# HWProgUSB.net
KiCad netlist of a schematic drawn in EAGLE
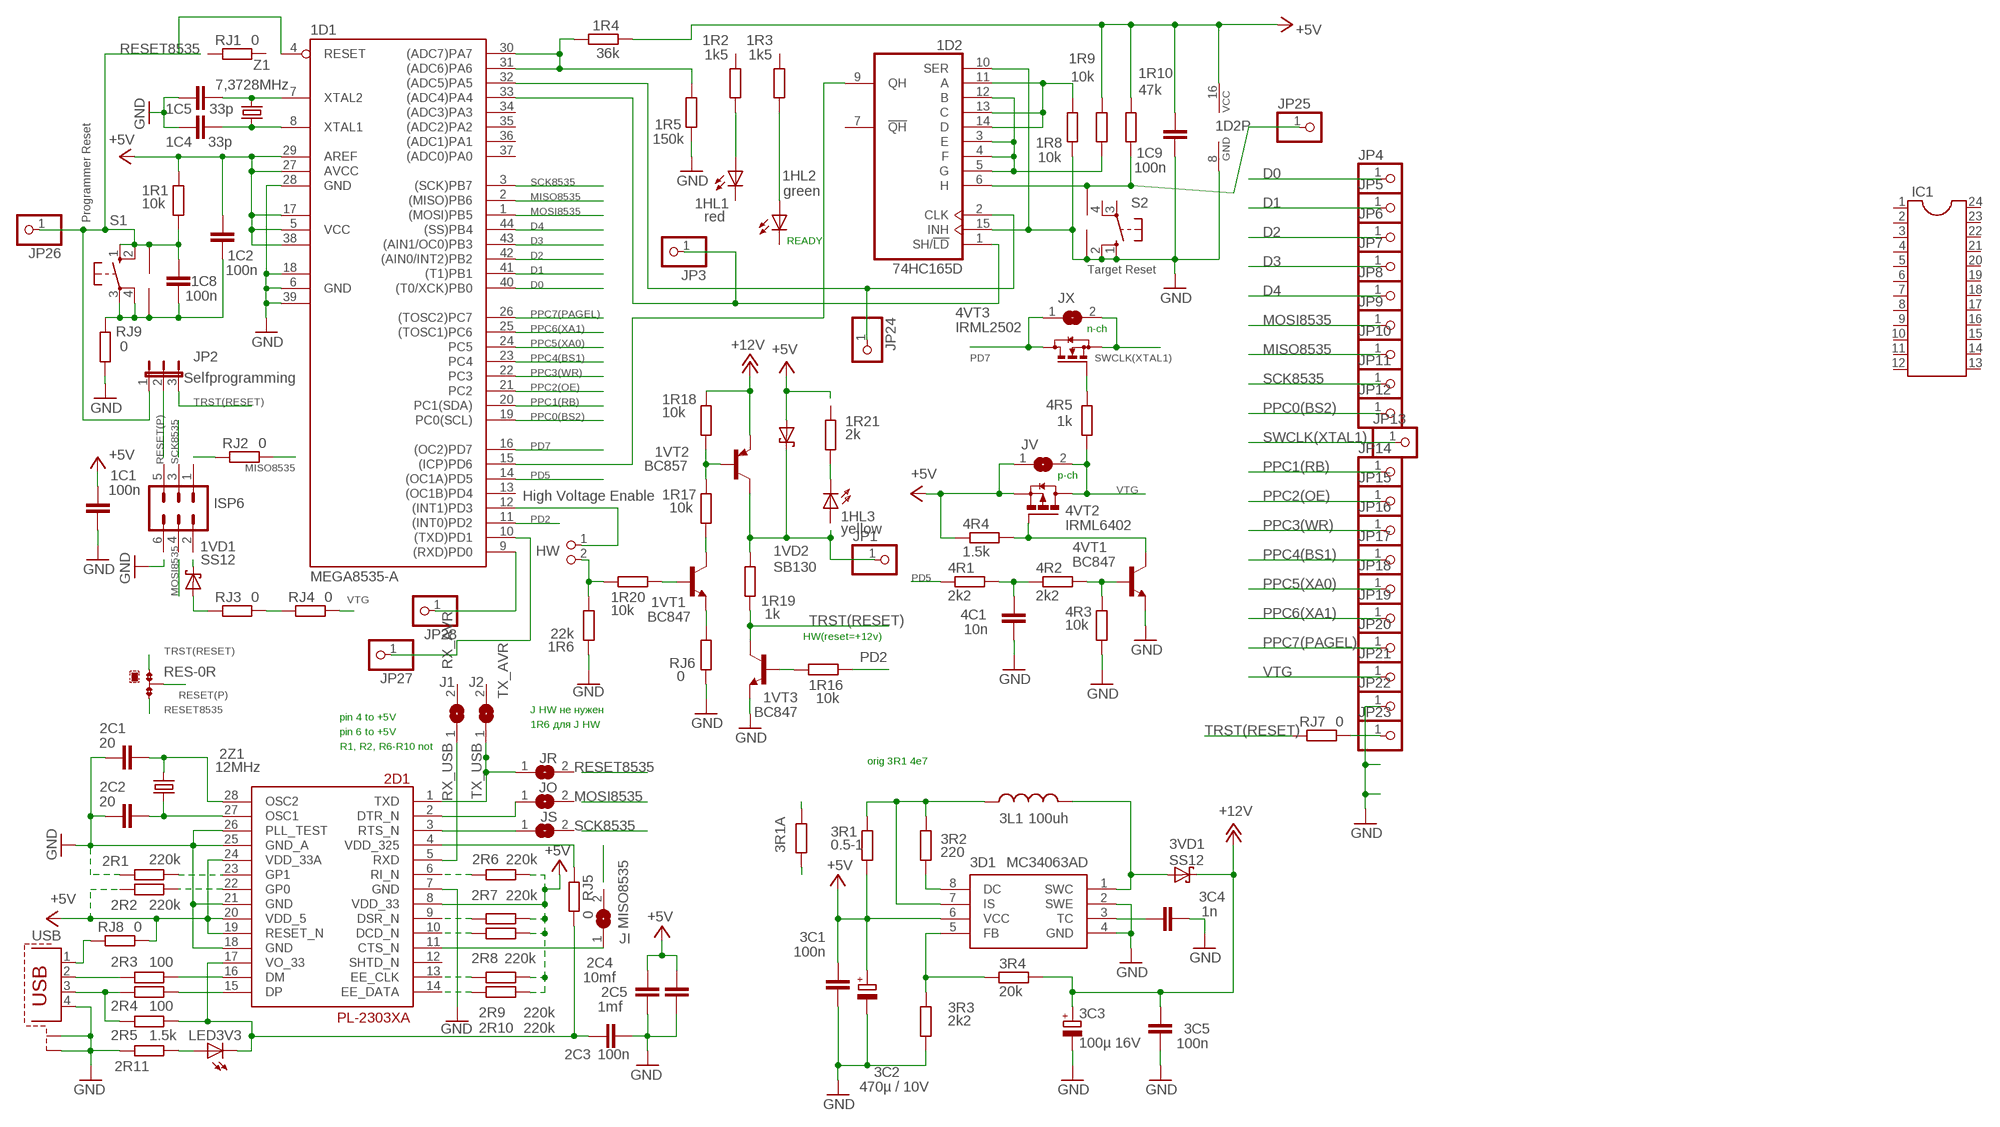
[diagram p0: schematic, sheet 1]

(export (version "E")
  (design (tool "Eeschema 10.0.6"))
  (components
    (comp (ref "1C1")
      (value "100n")
      (footprint "eagle-import:C0805")
      (libsource (lib "eagle-import") (part "rcl_C-EUC0805"))
    )
    (comp (ref "1C2")
      (value "100n")
      (footprint "eagle-import:C0805")
      (libsource (lib "eagle-import") (part "rcl_C-EUC0805"))
    )
    (comp (ref "1C4")
      (value "33p")
      (footprint "eagle-import:C0805")
      (libsource (lib "eagle-import") (part "rcl_C-EUC0805"))
    )
    (comp (ref "1C5")
      (value "33p")
      (footprint "eagle-import:C0805")
      (libsource (lib "eagle-import") (part "rcl_C-EUC0805"))
    )
    (comp (ref "1C8")
      (value "100n")
      (footprint "eagle-import:C0805")
      (libsource (lib "eagle-import") (part "rcl_C-EUC0805"))
    )
    (comp (ref "1C9")
      (value "100n")
      (footprint "eagle-import:C0805")
      (libsource (lib "eagle-import") (part "rcl_C-EUC0805"))
    )
    (comp (ref "1D1")
      (value "MEGA8535-A")
      (footprint "eagle-import:TQFP44")
      (fields (field (name "MPN") "ATMEGA8535-16AU"))
      (libsource (lib "eagle-import") (part "MEGA8535-A"))
    )
    (comp (ref "1D2")
      (value "74HC165D")
      (footprint "eagle-import:SO16")
      (libsource (lib "eagle-import") (part "74165DHC"))
    )
    (comp (ref "1HL1")
      (value "red")
      (footprint "eagle-import:LED5MM")
      (libsource (lib "eagle-import") (part "LED5MM"))
    )
    (comp (ref "1HL2")
      (value "green")
      (footprint "eagle-import:LED5MM")
      (libsource (lib "eagle-import") (part "LED5MM"))
    )
    (comp (ref "1HL3")
      (value "yellow")
      (footprint "eagle-import:LED5MM")
      (libsource (lib "eagle-import") (part "rc-elektronik_LED5MM"))
    )
    (comp (ref "1R1")
      (value "10k")
      (footprint "eagle-import:M0805")
      (libsource (lib "eagle-import") (part "R-EU_M0805"))
    )
    (comp (ref "1R2")
      (value "1k5")
      (footprint "eagle-import:M0805")
      (libsource (lib "eagle-import") (part "R-EU_M0805"))
    )
    (comp (ref "1R3")
      (value "1k5")
      (footprint "eagle-import:M0805")
      (libsource (lib "eagle-import") (part "R-EU_M0805"))
    )
    (comp (ref "1R4")
      (value "36k")
      (footprint "eagle-import:M0805")
      (libsource (lib "eagle-import") (part "R-EU_M0805"))
    )
    (comp (ref "1R5")
      (value "150k")
      (footprint "eagle-import:R1206")
      (libsource (lib "eagle-import") (part "R-EU_R1206"))
    )
    (comp (ref "1R6")
      (value "22k")
      (footprint "eagle-import:M1206")
      (libsource (lib "eagle-import") (part "R-EU_M1206"))
    )
    (comp (ref "1R8")
      (value "10k")
      (footprint "eagle-import:M0805")
      (libsource (lib "eagle-import") (part "R-EU_M0805"))
    )
    (comp (ref "1R9")
      (value "10k")
      (footprint "eagle-import:M0805")
      (libsource (lib "eagle-import") (part "R-EU_M0805"))
    )
    (comp (ref "1R10")
      (value "47k")
      (footprint "eagle-import:M0805")
      (libsource (lib "eagle-import") (part "R-EU_M0805"))
    )
    (comp (ref "1R16")
      (value "10k")
      (footprint "eagle-import:R0805")
      (libsource (lib "eagle-import") (part "R-EU_R0805"))
    )
    (comp (ref "1R17")
      (value "10k")
      (footprint "eagle-import:M0805")
      (libsource (lib "eagle-import") (part "R-EU_M0805"))
    )
    (comp (ref "1R18")
      (value "10k")
      (footprint "eagle-import:M0805")
      (libsource (lib "eagle-import") (part "R-EU_M0805"))
    )
    (comp (ref "1R19")
      (value "1k")
      (footprint "eagle-import:M0805")
      (libsource (lib "eagle-import") (part "R-EU_M0805"))
    )
    (comp (ref "1R20")
      (value "10k")
      (footprint "eagle-import:M0805")
      (libsource (lib "eagle-import") (part "R-EU_M0805"))
    )
    (comp (ref "1R21")
      (value "2k")
      (footprint "eagle-import:R1206W")
      (libsource (lib "eagle-import") (part "R-EU_R1206W"))
    )
    (comp (ref "1VD1")
      (value "SS12")
      (footprint "eagle-import:SMB")
      (libsource (lib "eagle-import") (part "SCHOTTKY-DIODESMD"))
    )
    (comp (ref "1VD2")
      (value "SB130")
      (footprint "eagle-import:SMB")
      (libsource (lib "eagle-import") (part "SCHOTTKY-DIODESMD"))
    )
    (comp (ref "1VT1")
      (value "BC847")
      (footprint "eagle-import:SOT23")
      (libsource (lib "eagle-import") (part "BC847"))
    )
    (comp (ref "1VT2")
      (value "BC857")
      (footprint "eagle-import:SOT23-BEC")
      (libsource (lib "eagle-import") (part "-PNP-SOT23-BECBC857A"))
    )
    (comp (ref "1VT3")
      (value "BC847")
      (footprint "eagle-import:SOT23")
      (libsource (lib "eagle-import") (part "BC847"))
    )
    (comp (ref "2C1")
      (value "20")
      (footprint "eagle-import:C0805")
      (libsource (lib "eagle-import") (part "resistor_C-EUC0805"))
    )
    (comp (ref "2C2")
      (value "20")
      (footprint "eagle-import:C0805")
      (libsource (lib "eagle-import") (part "resistor_C-EUC0805"))
    )
    (comp (ref "2C3")
      (value "100n")
      (footprint "eagle-import:C0805")
      (libsource (lib "eagle-import") (part "resistor_C-EUC0805"))
    )
    (comp (ref "2C4")
      (value "10mf")
      (footprint "eagle-import:C1210")
      (libsource (lib "eagle-import") (part "rcl_C-EUC1210"))
    )
    (comp (ref "2C5")
      (value "1mf")
      (footprint "eagle-import:C0805")
      (libsource (lib "eagle-import") (part "rcl_C-EUC0805"))
    )
    (comp (ref "2D1")
      (value "PL-2303XA")
      (footprint "eagle-import:SSOP28DB")
      (libsource (lib "eagle-import") (part "PL-2303XA"))
    )
    (comp (ref "2R1")
      (value "220k")
      (footprint "eagle-import:R0603")
      (libsource (lib "eagle-import") (part "resistor_R-EU_R0603"))
    )
    (comp (ref "2R2")
      (value "220k")
      (footprint "eagle-import:R1206W")
      (libsource (lib "eagle-import") (part "resistor_R-EU_R1206W"))
    )
    (comp (ref "2R3")
      (value "100")
      (footprint "eagle-import:R0603")
      (libsource (lib "eagle-import") (part "resistor_R-EU_R0603"))
    )
    (comp (ref "2R4")
      (value "100")
      (footprint "eagle-import:R0603")
      (libsource (lib "eagle-import") (part "resistor_R-EU_R0603"))
    )
    (comp (ref "2R5")
      (value "1.5k")
      (footprint "eagle-import:R0603")
      (libsource (lib "eagle-import") (part "resistor_R-EU_R0603"))
    )
    (comp (ref "2R6")
      (value "220k")
      (footprint "eagle-import:R1206W")
      (libsource (lib "eagle-import") (part "resistor_R-EU_R1206W"))
    )
    (comp (ref "2R7")
      (value "220k")
      (footprint "eagle-import:R0603")
      (libsource (lib "eagle-import") (part "resistor_R-EU_R0603"))
    )
    (comp (ref "2R8")
      (value "220k")
      (footprint "eagle-import:R0603")
      (libsource (lib "eagle-import") (part "resistor_R-EU_R0603"))
    )
    (comp (ref "2R9")
      (value "220k")
      (footprint "eagle-import:R0603")
      (libsource (lib "eagle-import") (part "resistor_R-EU_R0603"))
    )
    (comp (ref "2R10")
      (value "220k")
      (footprint "eagle-import:R0603")
      (libsource (lib "eagle-import") (part "resistor_R-EU_R0603"))
    )
    (comp (ref "2R11")
      (value "R-EU_R0603")
      (footprint "eagle-import:R0603")
      (libsource (lib "eagle-import") (part "resistor_R-EU_R0603"))
    )
    (comp (ref "2Z1")
      (value "12MHz")
      (footprint "eagle-import:HC49_S")
      (libsource (lib "eagle-import") (part "CRYSTALHC49S"))
    )
    (comp (ref "3C1")
      (value "100n")
      (footprint "eagle-import:C025-024X044")
      (libsource (lib "eagle-import") (part "C-EU025-024X044"))
    )
    (comp (ref "3C2")
      (value "470µ / 10V")
      (footprint "eagle-import:RCL_E3,5-8")
      (libsource (lib "eagle-import") (part "RCL_CPOL-EUE3.5-8"))
    )
    (comp (ref "3C3")
      (value "100µ 16V")
      (footprint "eagle-import:RCL_E3,5-8")
      (libsource (lib "eagle-import") (part "RCL_CPOL-EUE3.5-8"))
    )
    (comp (ref "3C4")
      (value "1n")
      (footprint "eagle-import:C025-025X050")
      (libsource (lib "eagle-import") (part "rcl_C-EU025-025X050"))
    )
    (comp (ref "3C5")
      (value "100n")
      (footprint "eagle-import:C025-025X050")
      (libsource (lib "eagle-import") (part "rcl_C-EU025-025X050"))
    )
    (comp (ref "3D1")
      (value "MC34063AD")
      (footprint "eagle-import:SOIC8")
      (libsource (lib "eagle-import") (part "MC34063AD"))
    )
    (comp (ref "3L1")
      (value "100uh")
      (footprint "eagle-import:0207_10")
      (libsource (lib "eagle-import") (part "L-US0207/10"))
    )
    (comp (ref "3R1")
      (value "0.5-1")
      (footprint "eagle-import:0204_7")
      (libsource (lib "eagle-import") (part "R-EU_0204/7"))
    )
    (comp (ref "3R1A")
      (value "R-EU_0204/7")
      (footprint "eagle-import:0204_7")
      (libsource (lib "eagle-import") (part "R-EU_0204/7"))
    )
    (comp (ref "3R2")
      (value "220")
      (footprint "eagle-import:0204_7")
      (libsource (lib "eagle-import") (part "R-EU_0204/7"))
    )
    (comp (ref "3R3")
      (value "2k2")
      (footprint "eagle-import:M0805")
      (libsource (lib "eagle-import") (part "R-EU_M0805"))
    )
    (comp (ref "3R4")
      (value "20k")
      (footprint "eagle-import:M0805")
      (libsource (lib "eagle-import") (part "R-EU_M0805"))
    )
    (comp (ref "3VD1")
      (value "SS12")
      (footprint "eagle-import:SMB")
      (libsource (lib "eagle-import") (part "SCHOTTKY-DIODESMD"))
    )
    (comp (ref "4C1")
      (value "10n")
      (footprint "eagle-import:C1206")
      (libsource (lib "eagle-import") (part "rcl_C-EUC1206"))
    )
    (comp (ref "4R1")
      (value "2k2")
      (footprint "eagle-import:M0805")
      (libsource (lib "eagle-import") (part "R-EU_M0805"))
    )
    (comp (ref "4R2")
      (value "2k2")
      (footprint "eagle-import:M1206")
      (libsource (lib "eagle-import") (part "R-EU_M1206"))
    )
    (comp (ref "4R3")
      (value "10k")
      (footprint "eagle-import:M0805")
      (libsource (lib "eagle-import") (part "R-EU_M0805"))
    )
    (comp (ref "4R4")
      (value "1.5k")
      (footprint "eagle-import:M0805")
      (libsource (lib "eagle-import") (part "R-EU_M0805"))
    )
    (comp (ref "4R5")
      (value "1k")
      (footprint "eagle-import:M0805")
      (libsource (lib "eagle-import") (part "R-EU_M0805"))
    )
    (comp (ref "4VT1")
      (value "BC847")
      (footprint "eagle-import:SOT23")
      (libsource (lib "eagle-import") (part "transistor-neu-to92_BC847"))
    )
    (comp (ref "4VT2")
      (value "IRML6402")
      (footprint "eagle-import:SUPER-SOT3")
      (libsource (lib "eagle-import") (part "FDN360P"))
    )
    (comp (ref "4VT3")
      (value "IRML2502")
      (footprint "eagle-import:SOT23")
      (libsource (lib "eagle-import") (part "BSS123"))
    )
    (comp (ref "HW")
      (value "High Voltage Enable")
      (footprint "eagle-import:PINHEAD_1X02")
      (libsource (lib "eagle-import") (part "PINHEAD_PINHD-1X2"))
    )
    (comp (ref "IC1")
      (value "DIL24-9")
      (footprint "eagle-import:DIL24-9")
      (libsource (lib "eagle-import") (part "DIL24-9"))
    )
    (comp (ref "ISP6")
      (value "MA03-2")
      (footprint "eagle-import:MA03-2")
      (libsource (lib "eagle-import") (part "MA03-2"))
    )
    (comp (ref "J1") (value "SJ") (footprint "eagle-import:SJ") (libsource (lib "eagle-import") (part "SJ")))
    (comp (ref "J2") (value "SJ") (footprint "eagle-import:SJ") (libsource (lib "eagle-import") (part "SJ")))
    (comp (ref "JI") (value "SJ") (footprint "eagle-import:SJ") (libsource (lib "eagle-import") (part "SJ")))
    (comp (ref "JO") (value "SJ") (footprint "eagle-import:SJ") (libsource (lib "eagle-import") (part "SJ")))
    (comp (ref "JP1")
      (value "PINHD-1X1")
      (footprint "eagle-import:1X01")
      (libsource (lib "eagle-import") (part "PINHD-1X1"))
    )
    (comp (ref "JP2")
      (value "Selfprogramming")
      (footprint "eagle-import:JUMPER_JP2")
      (libsource (lib "eagle-import") (part "JUMPER_JP2E"))
    )
    (comp (ref "JP3")
      (value "PINHD-1X1")
      (footprint "eagle-import:1X01")
      (libsource (lib "eagle-import") (part "PINHD-1X1"))
    )
    (comp (ref "JP4")
      (value "PINHD-1X1")
      (footprint "eagle-import:1X01")
      (libsource (lib "eagle-import") (part "PINHD-1X1"))
    )
    (comp (ref "JP5")
      (value "PINHD-1X1")
      (footprint "eagle-import:1X01")
      (libsource (lib "eagle-import") (part "PINHD-1X1"))
    )
    (comp (ref "JP6")
      (value "PINHD-1X1")
      (footprint "eagle-import:1X01")
      (libsource (lib "eagle-import") (part "PINHD-1X1"))
    )
    (comp (ref "JP7")
      (value "PINHD-1X1")
      (footprint "eagle-import:1X01")
      (libsource (lib "eagle-import") (part "PINHD-1X1"))
    )
    (comp (ref "JP8")
      (value "PINHD-1X1")
      (footprint "eagle-import:1X01")
      (libsource (lib "eagle-import") (part "PINHD-1X1"))
    )
    (comp (ref "JP9")
      (value "PINHD-1X1")
      (footprint "eagle-import:1X01")
      (libsource (lib "eagle-import") (part "PINHD-1X1"))
    )
    (comp (ref "JP10")
      (value "PINHD-1X1")
      (footprint "eagle-import:1X01")
      (libsource (lib "eagle-import") (part "PINHD-1X1"))
    )
    (comp (ref "JP11")
      (value "PINHD-1X1")
      (footprint "eagle-import:1X01")
      (libsource (lib "eagle-import") (part "PINHD-1X1"))
    )
    (comp (ref "JP12")
      (value "PINHD-1X1")
      (footprint "eagle-import:1X01")
      (libsource (lib "eagle-import") (part "PINHD-1X1"))
    )
    (comp (ref "JP13")
      (value "PINHD-1X1")
      (footprint "eagle-import:1X01")
      (libsource (lib "eagle-import") (part "PINHD-1X1"))
    )
    (comp (ref "JP14")
      (value "PINHD-1X1")
      (footprint "eagle-import:1X01")
      (libsource (lib "eagle-import") (part "PINHD-1X1"))
    )
    (comp (ref "JP15")
      (value "PINHD-1X1")
      (footprint "eagle-import:1X01")
      (libsource (lib "eagle-import") (part "PINHD-1X1"))
    )
    (comp (ref "JP16")
      (value "PINHD-1X1")
      (footprint "eagle-import:1X01")
      (libsource (lib "eagle-import") (part "PINHD-1X1"))
    )
    (comp (ref "JP17")
      (value "PINHD-1X1")
      (footprint "eagle-import:1X01")
      (libsource (lib "eagle-import") (part "PINHD-1X1"))
    )
    (comp (ref "JP18")
      (value "PINHD-1X1")
      (footprint "eagle-import:1X01")
      (libsource (lib "eagle-import") (part "PINHD-1X1"))
    )
    (comp (ref "JP19")
      (value "PINHD-1X1")
      (footprint "eagle-import:1X01")
      (libsource (lib "eagle-import") (part "PINHD-1X1"))
    )
    (comp (ref "JP20")
      (value "PINHD-1X1")
      (footprint "eagle-import:1X01")
      (libsource (lib "eagle-import") (part "PINHD-1X1"))
    )
    (comp (ref "JP21")
      (value "PINHD-1X1")
      (footprint "eagle-import:1X01")
      (libsource (lib "eagle-import") (part "PINHD-1X1"))
    )
    (comp (ref "JP22")
      (value "PINHD-1X1")
      (footprint "eagle-import:1X01")
      (libsource (lib "eagle-import") (part "PINHD-1X1"))
    )
    (comp (ref "JP23")
      (value "PINHD-1X1")
      (footprint "eagle-import:1X01")
      (libsource (lib "eagle-import") (part "PINHD-1X1"))
    )
    (comp (ref "JP24")
      (value "PINHD-1X1")
      (footprint "eagle-import:1X01")
      (libsource (lib "eagle-import") (part "PINHD-1X1"))
    )
    (comp (ref "JP25")
      (value "PINHD-1X1")
      (footprint "eagle-import:1X01")
      (libsource (lib "eagle-import") (part "PINHD-1X1"))
    )
    (comp (ref "JP26")
      (value "PINHD-1X1")
      (footprint "eagle-import:1X01")
      (libsource (lib "eagle-import") (part "PINHD-1X1"))
    )
    (comp (ref "JP27")
      (value "PINHD-1X1")
      (footprint "eagle-import:1X01")
      (libsource (lib "eagle-import") (part "PINHD-1X1"))
    )
    (comp (ref "JP28")
      (value "PINHD-1X1")
      (footprint "eagle-import:1X01")
      (libsource (lib "eagle-import") (part "PINHD-1X1"))
    )
    (comp (ref "JR") (value "SJ") (footprint "eagle-import:SJ") (libsource (lib "eagle-import") (part "SJ")))
    (comp (ref "JS") (value "SJ") (footprint "eagle-import:SJ") (libsource (lib "eagle-import") (part "SJ")))
    (comp (ref "JV") (value "SJ") (footprint "eagle-import:SJ") (libsource (lib "eagle-import") (part "SJ")))
    (comp (ref "JX") (value "SJ") (footprint "eagle-import:SJ") (libsource (lib "eagle-import") (part "SJ")))
    (comp (ref "LED3V3")
      (value "LEDCHIPLED_0603")
      (footprint "eagle-import:CHIPLED_0603")
      (libsource (lib "eagle-import") (part "LEDCHIPLED_0603"))
    )
    (comp (ref "RES")
      (value "0R-JUMPA")
      (footprint "eagle-import:A0R-JMP")
      (libsource (lib "eagle-import") (part "0R-JUMPA"))
    )
    (comp (ref "RJ1")
      (value "0")
      (footprint "eagle-import:R1206")
      (libsource (lib "eagle-import") (part "R-EU_R1206"))
    )
    (comp (ref "RJ2")
      (value "0")
      (footprint "eagle-import:R1206")
      (libsource (lib "eagle-import") (part "R-EU_R1206"))
    )
    (comp (ref "RJ3")
      (value "0")
      (footprint "eagle-import:R1206")
      (libsource (lib "eagle-import") (part "R-EU_R1206"))
    )
    (comp (ref "RJ4")
      (value "0")
      (footprint "eagle-import:R1206")
      (libsource (lib "eagle-import") (part "R-EU_R1206"))
    )
    (comp (ref "RJ5")
      (value "0")
      (footprint "eagle-import:R1206")
      (libsource (lib "eagle-import") (part "R-EU_R1206"))
    )
    (comp (ref "RJ6")
      (value "0")
      (footprint "eagle-import:R1206")
      (libsource (lib "eagle-import") (part "R-EU_R1206"))
    )
    (comp (ref "RJ7")
      (value "0")
      (footprint "eagle-import:R1206")
      (libsource (lib "eagle-import") (part "R-EU_R1206"))
    )
    (comp (ref "RJ8")
      (value "0")
      (footprint "eagle-import:R1206")
      (libsource (lib "eagle-import") (part "R-EU_R1206"))
    )
    (comp (ref "RJ9")
      (value "0")
      (footprint "eagle-import:R1206")
      (libsource (lib "eagle-import") (part "R-EU_R1206"))
    )
    (comp (ref "S1")
      (value "10-XX")
      (footprint "eagle-import:B3F-10XX")
      (libsource (lib "eagle-import") (part "10-XX"))
    )
    (comp (ref "S2")
      (value "10-XX")
      (footprint "eagle-import:B3F-10XX")
      (libsource (lib "eagle-import") (part "10-XX"))
    )
    (comp (ref "U$1")
      (value "5.08")
      (footprint "eagle-import:KEY")
      (libsource (lib "eagle-import") (part "5.08"))
    )
    (comp (ref "U$2")
      (value "5.08")
      (footprint "eagle-import:KEY")
      (libsource (lib "eagle-import") (part "5.08"))
    )
    (comp (ref "USB")
      (value "PROGRAMMER_PN61729-S")
      (footprint "eagle-import:PROGRAMMER_PN61729-S")
      (libsource (lib "eagle-import") (part "PROGRAMMER_PN61729-S"))
    )
    (comp (ref "Z1")
      (value "7,3728MHz")
      (footprint "eagle-import:HC49U-V")
      (libsource (lib "eagle-import") (part "CRYTALHC49U-V"))
    )
  )
  (nets
    (net (code "1") (name "+5V") (class "Default")
      (node (ref "1C1") (pin "2") (pinfunction "2_2") (pintype "passive"))
      (node (ref "1C2") (pin "2") (pinfunction "2_2") (pintype "passive"))
      (node (ref "1C9") (pin "1") (pinfunction "1_1") (pintype "passive"))
      (node (ref "1D1") (pin "17") (pinfunction "VCC1_17") (pintype "power_in"))
      (node (ref "1D1") (pin "27") (pinfunction "AVCC_27") (pintype "power_in"))
      (node (ref "1D1") (pin "29") (pinfunction "AREF_29") (pintype "passive"))
      (node (ref "1D1") (pin "38") (pinfunction "VCC2_38") (pintype "power_in"))
      (node (ref "1D1") (pin "5") (pinfunction "VCC_5") (pintype "power_in"))
      (node (ref "1D2") (pin "16") (pinfunction "VCC_16") (pintype "power_in"))
      (node (ref "1R1") (pin "2") (pinfunction "2_2") (pintype "passive"))
      (node (ref "1R10") (pin "1") (pinfunction "1_1") (pintype "passive"))
      (node (ref "1R4") (pin "2") (pinfunction "2_2") (pintype "passive"))
      (node (ref "1R9") (pin "1") (pinfunction "1_1") (pintype "passive"))
      (node (ref "1VD2") (pin "A") (pinfunction "A_A") (pintype "passive"))
      (node (ref "2C4") (pin "2") (pinfunction "2_2") (pintype "passive"))
      (node (ref "2C5") (pin "2") (pinfunction "2_2") (pintype "passive"))
      (node (ref "2D1") (pin "19") (pinfunction "RESET_N_19") (pintype "bidirectional"))
      (node (ref "2D1") (pin "20") (pinfunction "VDD_5_20") (pintype "bidirectional"))
      (node (ref "2D1") (pin "24") (pinfunction "VDD_33A_24") (pintype "bidirectional"))
      (node (ref "2D1") (pin "8") (pinfunction "VDD_33_8") (pintype "bidirectional"))
      (node (ref "2R10") (pin "1") (pinfunction "1_1") (pintype "passive"))
      (node (ref "2R2") (pin "1") (pinfunction "1_1") (pintype "passive"))
      (node (ref "2R6") (pin "2") (pinfunction "2_2") (pintype "passive"))
      (node (ref "2R7") (pin "1") (pinfunction "1_1") (pintype "passive"))
      (node (ref "2R8") (pin "1") (pinfunction "1_1") (pintype "passive"))
      (node (ref "2R9") (pin "1") (pinfunction "1_1") (pintype "passive"))
      (node (ref "3C1") (pin "1") (pinfunction "1_1") (pintype "passive"))
      (node (ref "3C2") (pin "+") (pinfunction "+_+") (pintype "passive"))
      (node (ref "3D1") (pin "6") (pinfunction "VCC_6") (pintype "passive"))
      (node (ref "3R1") (pin "1") (pinfunction "1_1") (pintype "passive"))
      (node (ref "3R1A") (pin "1") (pinfunction "1_1") (pintype "passive"))
      (node (ref "4R4") (pin "1") (pinfunction "1_1") (pintype "passive"))
      (node (ref "4VT2") (pin "2") (pinfunction "S_2") (pintype "passive"))
      (node (ref "JV") (pin "1") (pinfunction "1_1") (pintype "passive"))
      (node (ref "RJ8") (pin "2") (pinfunction "2_2") (pintype "passive"))
    )
    (net (code "2") (name "+12V") (class "Default")
      (node (ref "1R18") (pin "2") (pinfunction "2_2") (pintype "passive"))
      (node (ref "1VT2") (pin "E") (pinfunction "E_E") (pintype "passive"))
      (node (ref "3C3") (pin "+") (pinfunction "+_+") (pintype "passive"))
      (node (ref "3C5") (pin "2") (pinfunction "2_2") (pintype "passive"))
      (node (ref "3R4") (pin "2") (pinfunction "2_2") (pintype "passive"))
      (node (ref "3VD1") (pin "C") (pinfunction "C_C") (pintype "passive"))
    )
    (net (code "3") (name "/D0") (class "Default")
      (node (ref "1D1") (pin "40") (pinfunction "(T0/XCK)PB0_40") (pintype "bidirectional"))
      (node (ref "JP4") (pin "1") (pinfunction "1_1") (pintype "passive"))
    )
    (net (code "4") (name "/D1") (class "Default")
      (node (ref "1D1") (pin "41") (pinfunction "(T1)PB1_41") (pintype "bidirectional"))
      (node (ref "JP5") (pin "1") (pinfunction "1_1") (pintype "passive"))
    )
    (net (code "5") (name "/D2") (class "Default")
      (node (ref "1D1") (pin "42") (pinfunction "(AIN0/INT2)PB2_42") (pintype "bidirectional"))
      (node (ref "JP6") (pin "1") (pinfunction "1_1") (pintype "passive"))
    )
    (net (code "6") (name "/D3") (class "Default")
      (node (ref "1D1") (pin "43") (pinfunction "(AIN1/OC0)PB3_43") (pintype "bidirectional"))
      (node (ref "JP7") (pin "1") (pinfunction "1_1") (pintype "passive"))
    )
    (net (code "7") (name "/D4") (class "Default")
      (node (ref "1D1") (pin "44") (pinfunction "(SS)PB4_44") (pintype "bidirectional"))
      (node (ref "JP8") (pin "1") (pinfunction "1_1") (pintype "passive"))
    )
    (net (code "8") (name "/MISO8535") (class "Default")
      (node (ref "1D1") (pin "2") (pinfunction "(MISO)PB6_2") (pintype "bidirectional"))
      (node (ref "JP10") (pin "1") (pinfunction "1_1") (pintype "passive"))
      (node (ref "RJ2") (pin "2") (pinfunction "2_2") (pintype "passive"))
    )
    (net (code "9") (name "/MOSI8535") (class "Default")
      (node (ref "1D1") (pin "1") (pinfunction "(MOSI)PB5_1") (pintype "bidirectional"))
      (node (ref "JP9") (pin "1") (pinfunction "1_1") (pintype "passive"))
    )
    (net (code "10") (name "/N$105") (class "Default")
      (node (ref "3D1") (pin "7") (pinfunction "IS_7") (pintype "passive"))
      (node (ref "3L1") (pin "1") (pinfunction "1_1") (pintype "passive"))
      (node (ref "3R1") (pin "2") (pinfunction "2_2") (pintype "passive"))
      (node (ref "3R1A") (pin "2") (pinfunction "2_2") (pintype "passive"))
      (node (ref "3R2") (pin "2") (pinfunction "2_2") (pintype "passive"))
    )
    (net (code "11") (name "/PD2") (class "Default")
      (node (ref "1D1") (pin "11") (pinfunction "(INT0)PD2_11") (pintype "bidirectional"))
      (node (ref "1R16") (pin "1") (pinfunction "1_1") (pintype "passive"))
    )
    (net (code "12") (name "/PD5") (class "Default")
      (node (ref "1D1") (pin "14") (pinfunction "(OC1A)PD5_14") (pintype "bidirectional"))
      (node (ref "4R1") (pin "1") (pinfunction "1_1") (pintype "passive"))
    )
    (net (code "13") (name "/PD7") (class "Default")
      (node (ref "1D1") (pin "16") (pinfunction "(OC2)PD7_16") (pintype "bidirectional"))
      (node (ref "4VT3") (pin "3") (pinfunction "D_3") (pintype "passive"))
      (node (ref "JX") (pin "1") (pinfunction "1_1") (pintype "passive"))
    )
    (net (code "14") (name "/PPC0(BS2)") (class "Default")
      (node (ref "1D1") (pin "19") (pinfunction "PC0(SCL)_19") (pintype "bidirectional"))
      (node (ref "JP12") (pin "1") (pinfunction "1_1") (pintype "passive"))
    )
    (net (code "15") (name "/PPC1(RB)") (class "Default")
      (node (ref "1D1") (pin "20") (pinfunction "PC1(SDA)_20") (pintype "bidirectional"))
      (node (ref "JP14") (pin "1") (pinfunction "1_1") (pintype "passive"))
    )
    (net (code "16") (name "/PPC2(OE)") (class "Default")
      (node (ref "1D1") (pin "21") (pinfunction "PC2_21") (pintype "bidirectional"))
      (node (ref "JP15") (pin "1") (pinfunction "1_1") (pintype "passive"))
    )
    (net (code "17") (name "/PPC3(WR)") (class "Default")
      (node (ref "1D1") (pin "22") (pinfunction "PC3_22") (pintype "bidirectional"))
      (node (ref "JP16") (pin "1") (pinfunction "1_1") (pintype "passive"))
    )
    (net (code "18") (name "/PPC4(BS1)") (class "Default")
      (node (ref "1D1") (pin "23") (pinfunction "PC4_23") (pintype "bidirectional"))
      (node (ref "JP17") (pin "1") (pinfunction "1_1") (pintype "passive"))
    )
    (net (code "19") (name "/PPC5(XA0)") (class "Default")
      (node (ref "1D1") (pin "24") (pinfunction "PC5_24") (pintype "bidirectional"))
      (node (ref "JP18") (pin "1") (pinfunction "1_1") (pintype "passive"))
    )
    (net (code "20") (name "/PPC6(XA1)") (class "Default")
      (node (ref "1D1") (pin "25") (pinfunction "(TOSC1)PC6_25") (pintype "bidirectional"))
      (node (ref "JP19") (pin "1") (pinfunction "1_1") (pintype "passive"))
    )
    (net (code "21") (name "/PPC7(PAGEL)") (class "Default")
      (node (ref "1D1") (pin "26") (pinfunction "(TOSC2)PC7_26") (pintype "bidirectional"))
      (node (ref "JP20") (pin "1") (pinfunction "1_1") (pintype "passive"))
    )
    (net (code "22") (name "/RESET(P)") (class "Default")
      (node (ref "JP2") (pin "2") (pinfunction "2_2") (pintype "passive"))
      (node (ref "RES") (pin "2") (pinfunction "2_2") (pintype "passive"))
    )
    (net (code "23") (name "/RESET8535") (class "Default")
      (node (ref "1C8") (pin "2") (pinfunction "2_2") (pintype "passive"))
      (node (ref "1D1") (pin "4") (pinfunction "RESET_4") (pintype "input"))
      (node (ref "1R1") (pin "1") (pinfunction "1_1") (pintype "passive"))
      (node (ref "JP2") (pin "1") (pinfunction "1_1") (pintype "passive"))
      (node (ref "JP26") (pin "1") (pinfunction "1_1") (pintype "passive"))
      (node (ref "RES") (pin "3") (pinfunction "3_3") (pintype "passive"))
      (node (ref "S1") (pin "1") (pinfunction "S_1") (pintype "passive"))
      (node (ref "S1") (pin "2") (pinfunction "S1_2") (pintype "passive"))
      (node (ref "U$1") (pin "P$2") (pinfunction "P$2_P$2") (pintype "bidirectional"))
    )
    (net (code "24") (name "/RX_AVR") (class "Default")
      (node (ref "1D1") (pin "10") (pinfunction "(TXD)PD1_10") (pintype "bidirectional"))
      (node (ref "JP27") (pin "1") (pinfunction "1_1") (pintype "passive"))
    )
    (net (code "25") (name "/RX_USB") (class "Default")
      (node (ref "2D1") (pin "5") (pinfunction "RXD_5") (pintype "bidirectional"))
      (node (ref "J1") (pin "1") (pinfunction "1_1") (pintype "passive"))
    )
    (net (code "26") (name "/SCK8535") (class "Default")
      (node (ref "1D1") (pin "3") (pinfunction "(SCK)PB7_3") (pintype "bidirectional"))
      (node (ref "JP11") (pin "1") (pinfunction "1_1") (pintype "passive"))
    )
    (net (code "27") (name "/SWCLK(XTAL1)") (class "Default")
      (node (ref "4VT3") (pin "2") (pinfunction "S_2") (pintype "passive"))
      (node (ref "JP13") (pin "1") (pinfunction "1_1") (pintype "passive"))
      (node (ref "JX") (pin "2") (pinfunction "2_2") (pintype "passive"))
    )
    (net (code "28") (name "/TRST(RESET)") (class "Default")
      (node (ref "1R19") (pin "1") (pinfunction "1_1") (pintype "passive"))
      (node (ref "1VT3") (pin "3") (pinfunction "C_3") (pintype "passive"))
      (node (ref "JP2") (pin "3") (pinfunction "3_3") (pintype "passive"))
      (node (ref "RES") (pin "1") (pinfunction "1_1") (pintype "passive"))
      (node (ref "RJ7") (pin "1") (pinfunction "1_1") (pintype "passive"))
    )
    (net (code "29") (name "/TX_AVR") (class "Default")
      (node (ref "1D1") (pin "9") (pinfunction "(RXD)PD0_9") (pintype "bidirectional"))
      (node (ref "JP28") (pin "1") (pinfunction "1_1") (pintype "passive"))
    )
    (net (code "30") (name "/TX_USB") (class "Default")
      (node (ref "2D1") (pin "1") (pinfunction "TXD_1") (pintype "bidirectional"))
      (node (ref "J2") (pin "1") (pinfunction "1_1") (pintype "passive"))
      (node (ref "JR") (pin "1") (pinfunction "1_1") (pintype "passive"))
    )
    (net (code "31") (name "/VTG") (class "Default")
      (node (ref "4R5") (pin "1") (pinfunction "1_1") (pintype "passive"))
      (node (ref "4VT2") (pin "3") (pinfunction "D_3") (pintype "passive"))
      (node (ref "JP21") (pin "1") (pinfunction "1_1") (pintype "passive"))
      (node (ref "JV") (pin "2") (pinfunction "2_2") (pintype "passive"))
      (node (ref "RJ4") (pin "2") (pinfunction "2_2") (pintype "passive"))
    )
    (net (code "32") (name "GND") (class "Default")
      (node (ref "1C1") (pin "1") (pinfunction "1_1") (pintype "passive"))
      (node (ref "1C4") (pin "1") (pinfunction "1_1") (pintype "passive"))
      (node (ref "1C5") (pin "1") (pinfunction "1_1") (pintype "passive"))
      (node (ref "1C9") (pin "2") (pinfunction "2_2") (pintype "passive"))
      (node (ref "1D1") (pin "18") (pinfunction "GND1_18") (pintype "power_in"))
      (node (ref "1D1") (pin "28") (pinfunction "GND_28") (pintype "power_in"))
      (node (ref "1D1") (pin "39") (pinfunction "GND2_39") (pintype "power_in"))
      (node (ref "1D1") (pin "6") (pinfunction "GND_6") (pintype "power_in"))
      (node (ref "1D2") (pin "10") (pinfunction "SER_10") (pintype "input"))
      (node (ref "1D2") (pin "15") (pinfunction "INH_15") (pintype "input"))
      (node (ref "1D2") (pin "8") (pinfunction "GND_8") (pintype "power_in"))
      (node (ref "1R5") (pin "1") (pinfunction "1_1") (pintype "passive"))
      (node (ref "1R6") (pin "1") (pinfunction "1_1") (pintype "passive"))
      (node (ref "1R8") (pin "1") (pinfunction "1_1") (pintype "passive"))
      (node (ref "1VT3") (pin "2") (pinfunction "E_2") (pintype "passive"))
      (node (ref "2C1") (pin "1") (pinfunction "1_1") (pintype "passive"))
      (node (ref "2C2") (pin "1") (pinfunction "1_1") (pintype "passive"))
      (node (ref "2C3") (pin "2") (pinfunction "2_2") (pintype "passive"))
      (node (ref "2C4") (pin "1") (pinfunction "1_1") (pintype "passive"))
      (node (ref "2C5") (pin "1") (pinfunction "1_1") (pintype "passive"))
      (node (ref "2D1") (pin "18") (pinfunction "GND_18") (pintype "bidirectional"))
      (node (ref "2D1") (pin "21") (pinfunction "GND_21") (pintype "bidirectional"))
      (node (ref "2D1") (pin "25") (pinfunction "GND_A_25") (pintype "bidirectional"))
      (node (ref "2D1") (pin "26") (pinfunction "PLL_TEST_26") (pintype "bidirectional"))
      (node (ref "2D1") (pin "7") (pinfunction "GND_7") (pintype "bidirectional"))
      (node (ref "2R1") (pin "1") (pinfunction "1_1") (pintype "passive"))
      (node (ref "2R11") (pin "2") (pinfunction "2_2") (pintype "passive"))
      (node (ref "3C1") (pin "2") (pinfunction "2_2") (pintype "passive"))
      (node (ref "3C2") (pin "-") (pinfunction "-_-") (pintype "passive"))
      (node (ref "3C3") (pin "-") (pinfunction "-_-") (pintype "passive"))
      (node (ref "3C4") (pin "2") (pinfunction "2_2") (pintype "passive"))
      (node (ref "3C5") (pin "1") (pinfunction "1_1") (pintype "passive"))
      (node (ref "3D1") (pin "2") (pinfunction "SWE_2") (pintype "passive"))
      (node (ref "3D1") (pin "4") (pinfunction "GND_4") (pintype "passive"))
      (node (ref "3R3") (pin "1") (pinfunction "1_1") (pintype "passive"))
      (node (ref "4C1") (pin "1") (pinfunction "1_1") (pintype "passive"))
      (node (ref "4R3") (pin "1") (pinfunction "1_1") (pintype "passive"))
      (node (ref "4VT1") (pin "2") (pinfunction "E_2") (pintype "passive"))
      (node (ref "JP22") (pin "1") (pinfunction "1_1") (pintype "passive"))
      (node (ref "RJ6") (pin "1") (pinfunction "1_1") (pintype "passive"))
      (node (ref "RJ9") (pin "1") (pinfunction "1_1") (pintype "passive"))
      (node (ref "S2") (pin "1") (pinfunction "S_1") (pintype "passive"))
      (node (ref "S2") (pin "2") (pinfunction "S1_2") (pintype "passive"))
      (node (ref "U$2") (pin "P$1") (pinfunction "P$1_P$1") (pintype "bidirectional"))
      (node (ref "USB") (pin "4") (pinfunction "4_4") (pintype "passive"))
      (node (ref "USB") (pin "S1") (pinfunction "S1_S1") (pintype "passive"))
      (node (ref "USB") (pin "S2") (pinfunction "S2_S2") (pintype "passive"))
    )
    (net (code "33") (name "Net-(1D1-(ADC4)PA4)") (class "Default")
      (node (ref "1D1") (pin "33") (pinfunction "(ADC4)PA4_33") (pintype "bidirectional"))
      (node (ref "1D2") (pin "1") (pinfunction "SH/~{LD}_1") (pintype "input"))
      (node (ref "JP3") (pin "1") (pinfunction "1_1") (pintype "passive"))
    )
    (net (code "34") (name "Net-(1D1-(ADC5)PA5)") (class "Default")
      (node (ref "1D1") (pin "32") (pinfunction "(ADC5)PA5_32") (pintype "bidirectional"))
      (node (ref "1D2") (pin "2") (pinfunction "CLK_2") (pintype "input"))
      (node (ref "JP24") (pin "1") (pinfunction "1_1") (pintype "passive"))
    )
    (net (code "35") (name "Net-(1D1-(ADC6)PA6)") (class "Default")
      (node (ref "1D1") (pin "30") (pinfunction "(ADC7)PA7_30") (pintype "bidirectional"))
      (node (ref "1D1") (pin "31") (pinfunction "(ADC6)PA6_31") (pintype "bidirectional"))
      (node (ref "1R4") (pin "1") (pinfunction "1_1") (pintype "passive"))
      (node (ref "1R5") (pin "2") (pinfunction "2_2") (pintype "passive"))
    )
    (net (code "36") (name "Net-(1D1-(ICP)PD6)") (class "Default")
      (node (ref "1D1") (pin "15") (pinfunction "(ICP)PD6_15") (pintype "bidirectional"))
      (node (ref "1D2") (pin "9") (pinfunction "QH_9") (pintype "output"))
    )
    (net (code "37") (name "Net-(1D1-(INT1)PD3)") (class "Default")
      (node (ref "1D1") (pin "12") (pinfunction "(INT1)PD3_12") (pintype "bidirectional"))
      (node (ref "HW") (pin "1") (pinfunction "1_1") (pintype "passive"))
    )
    (net (code "38") (name "Net-(1D1-XTAL1)") (class "Default")
      (node (ref "1C4") (pin "2") (pinfunction "2_2") (pintype "passive"))
      (node (ref "1D1") (pin "8") (pinfunction "XTAL1_8") (pintype "bidirectional"))
      (node (ref "Z1") (pin "1") (pinfunction "1_1") (pintype "passive"))
    )
    (net (code "39") (name "Net-(1D1-XTAL2)") (class "Default")
      (node (ref "1C5") (pin "2") (pinfunction "2_2") (pintype "passive"))
      (node (ref "1D1") (pin "7") (pinfunction "XTAL2_7") (pintype "bidirectional"))
      (node (ref "Z1") (pin "2") (pinfunction "2_2") (pintype "passive"))
    )
    (net (code "40") (name "Net-(1D2A-A)") (class "Default")
      (node (ref "1D2") (pin "11") (pinfunction "A_11") (pintype "input"))
      (node (ref "1D2") (pin "13") (pinfunction "C_13") (pintype "input"))
      (node (ref "1D2") (pin "14") (pinfunction "D_14") (pintype "input"))
      (node (ref "1R8") (pin "2") (pinfunction "2_2") (pintype "passive"))
    )
    (net (code "41") (name "Net-(1D2A-B)") (class "Default")
      (node (ref "1D2") (pin "12") (pinfunction "B_12") (pintype "input"))
      (node (ref "1D2") (pin "3") (pinfunction "E_3") (pintype "input"))
      (node (ref "1D2") (pin "4") (pinfunction "F_4") (pintype "input"))
      (node (ref "1D2") (pin "5") (pinfunction "G_5") (pintype "input"))
      (node (ref "1R9") (pin "2") (pinfunction "2_2") (pintype "passive"))
    )
    (net (code "42") (name "Net-(1D2A-H)") (class "Default")
      (node (ref "1D2") (pin "6") (pinfunction "H_6") (pintype "input"))
      (node (ref "1R10") (pin "2") (pinfunction "2_2") (pintype "passive"))
      (node (ref "JP25") (pin "1") (pinfunction "1_1") (pintype "passive"))
      (node (ref "U$2") (pin "P$2") (pinfunction "P$2_P$2") (pintype "bidirectional"))
    )
    (net (code "43") (name "Net-(1HL1-PadA)") (class "Default")
      (node (ref "1HL1") (pin "A") (pinfunction "A_A") (pintype "passive"))
      (node (ref "1R2") (pin "1") (pinfunction "1_1") (pintype "passive"))
    )
    (net (code "44") (name "Net-(1HL2-PadA)") (class "Default")
      (node (ref "1HL2") (pin "A") (pinfunction "A_A") (pintype "passive"))
      (node (ref "1R3") (pin "1") (pinfunction "1_1") (pintype "passive"))
    )
    (net (code "45") (name "Net-(1HL3-C)") (class "Default")
      (node (ref "1HL3") (pin "K") (pinfunction "C_K") (pintype "passive"))
      (node (ref "1R21") (pin "1") (pinfunction "1_1") (pintype "passive"))
    )
    (net (code "46") (name "Net-(1R17-Pad2)") (class "Default")
      (node (ref "1R17") (pin "2") (pinfunction "2_2") (pintype "passive"))
      (node (ref "1R18") (pin "1") (pinfunction "1_1") (pintype "passive"))
      (node (ref "1VT2") (pin "B") (pinfunction "B_B") (pintype "passive"))
    )
    (net (code "47") (name "Net-(1R19-Pad2)") (class "Default")
      (node (ref "1R19") (pin "2") (pinfunction "2_2") (pintype "passive"))
      (node (ref "1VD2") (pin "C") (pinfunction "C_C") (pintype "passive"))
      (node (ref "1VT2") (pin "C") (pinfunction "C_C") (pintype "passive"))
      (node (ref "JP1") (pin "1") (pinfunction "1_1") (pintype "passive"))
    )
    (net (code "48") (name "Net-(1R20-Pad2)") (class "Default")
      (node (ref "1R20") (pin "2") (pinfunction "2_2") (pintype "passive"))
      (node (ref "1R6") (pin "2") (pinfunction "2_2") (pintype "passive"))
      (node (ref "HW") (pin "2") (pinfunction "2_2") (pintype "passive"))
    )
    (net (code "49") (name "Net-(1VD1-PadA)") (class "Default")
      (node (ref "1VD1") (pin "A") (pinfunction "A_A") (pintype "passive"))
      (node (ref "RJ3") (pin "1") (pinfunction "1_1") (pintype "passive"))
    )
    (net (code "50") (name "Net-(1VT1-B)") (class "Default")
      (node (ref "1R20") (pin "1") (pinfunction "1_1") (pintype "passive"))
      (node (ref "1VT1") (pin "1") (pinfunction "B_1") (pintype "passive"))
    )
    (net (code "51") (name "Net-(1VT1-C)") (class "Default")
      (node (ref "1R17") (pin "1") (pinfunction "1_1") (pintype "passive"))
      (node (ref "1VT1") (pin "3") (pinfunction "C_3") (pintype "passive"))
    )
    (net (code "52") (name "Net-(1VT1-E)") (class "Default")
      (node (ref "1VT1") (pin "2") (pinfunction "E_2") (pintype "passive"))
      (node (ref "RJ6") (pin "2") (pinfunction "2_2") (pintype "passive"))
    )
    (net (code "53") (name "Net-(1VT3-B)") (class "Default")
      (node (ref "1R16") (pin "2") (pinfunction "2_2") (pintype "passive"))
      (node (ref "1VT3") (pin "1") (pinfunction "B_1") (pintype "passive"))
    )
    (net (code "54") (name "Net-(2D1-CTS_N)") (class "Default")
      (node (ref "2D1") (pin "11") (pinfunction "CTS_N_11") (pintype "bidirectional"))
      (node (ref "JI") (pin "1") (pinfunction "1_1") (pintype "passive"))
    )
    (net (code "55") (name "Net-(2D1-DCD_N)") (class "Default")
      (node (ref "2D1") (pin "10") (pinfunction "DCD_N_10") (pintype "bidirectional"))
      (node (ref "2R8") (pin "2") (pinfunction "2_2") (pintype "passive"))
    )
    (net (code "56") (name "Net-(2D1-DM)") (class "Default")
      (node (ref "2D1") (pin "16") (pinfunction "DM_16") (pintype "bidirectional"))
      (node (ref "2R3") (pin "2") (pinfunction "2_2") (pintype "passive"))
    )
    (net (code "57") (name "Net-(2D1-DP)") (class "Default")
      (node (ref "2D1") (pin "15") (pinfunction "DP_15") (pintype "bidirectional"))
      (node (ref "2R4") (pin "2") (pinfunction "2_2") (pintype "passive"))
    )
    (net (code "58") (name "Net-(2D1-DSR_N)") (class "Default")
      (node (ref "2D1") (pin "9") (pinfunction "DSR_N_9") (pintype "bidirectional"))
      (node (ref "2R7") (pin "2") (pinfunction "2_2") (pintype "passive"))
    )
    (net (code "59") (name "Net-(2D1-DTR_N)") (class "Default")
      (node (ref "2D1") (pin "2") (pinfunction "DTR_N_2") (pintype "bidirectional"))
      (node (ref "JO") (pin "1") (pinfunction "1_1") (pintype "passive"))
    )
    (net (code "60") (name "Net-(2D1-EE_CLK)") (class "Default")
      (node (ref "2D1") (pin "13") (pinfunction "EE_CLK_13") (pintype "bidirectional"))
      (node (ref "2R9") (pin "2") (pinfunction "2_2") (pintype "passive"))
    )
    (net (code "61") (name "Net-(2D1-EE_DATA)") (class "Default")
      (node (ref "2D1") (pin "14") (pinfunction "EE_DATA_14") (pintype "bidirectional"))
      (node (ref "2R10") (pin "2") (pinfunction "2_2") (pintype "passive"))
    )
    (net (code "62") (name "Net-(2D1-GP0)") (class "Default")
      (node (ref "2D1") (pin "22") (pinfunction "GP0_22") (pintype "bidirectional"))
      (node (ref "2R2") (pin "2") (pinfunction "2_2") (pintype "passive"))
    )
    (net (code "63") (name "Net-(2D1-GP1)") (class "Default")
      (node (ref "2D1") (pin "23") (pinfunction "GP1_23") (pintype "bidirectional"))
      (node (ref "2R1") (pin "2") (pinfunction "2_2") (pintype "passive"))
    )
    (net (code "64") (name "Net-(2D1-OSC1)") (class "Default")
      (node (ref "2C2") (pin "2") (pinfunction "2_2") (pintype "passive"))
      (node (ref "2D1") (pin "27") (pinfunction "OSC1_27") (pintype "bidirectional"))
      (node (ref "2Z1") (pin "1") (pinfunction "1_1") (pintype "passive"))
    )
    (net (code "65") (name "Net-(2D1-OSC2)") (class "Default")
      (node (ref "2C1") (pin "2") (pinfunction "2_2") (pintype "passive"))
      (node (ref "2D1") (pin "28") (pinfunction "OSC2_28") (pintype "bidirectional"))
      (node (ref "2Z1") (pin "2") (pinfunction "2_2") (pintype "passive"))
    )
    (net (code "66") (name "Net-(2D1-RI_N)") (class "Default")
      (node (ref "2D1") (pin "6") (pinfunction "RI_N_6") (pintype "bidirectional"))
      (node (ref "2R6") (pin "1") (pinfunction "1_1") (pintype "passive"))
    )
    (net (code "67") (name "Net-(2D1-RTS_N)") (class "Default")
      (node (ref "2D1") (pin "3") (pinfunction "RTS_N_3") (pintype "bidirectional"))
      (node (ref "JS") (pin "1") (pinfunction "1_1") (pintype "passive"))
    )
    (net (code "68") (name "Net-(2D1-VDD_325)") (class "Default")
      (node (ref "2D1") (pin "4") (pinfunction "VDD_325_4") (pintype "bidirectional"))
      (node (ref "RJ5") (pin "1") (pinfunction "1_1") (pintype "passive"))
    )
    (net (code "69") (name "Net-(2D1-VO_33)") (class "Default")
      (node (ref "2C3") (pin "1") (pinfunction "1_1") (pintype "passive"))
      (node (ref "2D1") (pin "17") (pinfunction "VO_33_17") (pintype "bidirectional"))
      (node (ref "2R5") (pin "1") (pinfunction "1_1") (pintype "passive"))
      (node (ref "LED3V3") (pin "C") (pinfunction "C_C") (pintype "passive"))
      (node (ref "RJ5") (pin "2") (pinfunction "2_2") (pintype "passive"))
    )
    (net (code "70") (name "Net-(2R3-Pad1)") (class "Default")
      (node (ref "2R3") (pin "1") (pinfunction "1_1") (pintype "passive"))
      (node (ref "USB") (pin "2") (pinfunction "2_2") (pintype "passive"))
    )
    (net (code "71") (name "Net-(2R4-Pad1)") (class "Default")
      (node (ref "2R4") (pin "1") (pinfunction "1_1") (pintype "passive"))
      (node (ref "2R5") (pin "2") (pinfunction "2_2") (pintype "passive"))
      (node (ref "USB") (pin "3") (pinfunction "3_3") (pintype "passive"))
    )
    (net (code "72") (name "Net-(2R11-Pad1)") (class "Default")
      (node (ref "2R11") (pin "1") (pinfunction "1_1") (pintype "passive"))
      (node (ref "LED3V3") (pin "A") (pinfunction "A_A") (pintype "passive"))
    )
    (net (code "73") (name "Net-(3D1-DC)") (class "Default")
      (node (ref "3D1") (pin "8") (pinfunction "DC_8") (pintype "passive"))
      (node (ref "3R2") (pin "1") (pinfunction "1_1") (pintype "passive"))
    )
    (net (code "74") (name "Net-(3D1-FB)") (class "Default")
      (node (ref "3D1") (pin "5") (pinfunction "FB_5") (pintype "passive"))
      (node (ref "3R3") (pin "2") (pinfunction "2_2") (pintype "passive"))
      (node (ref "3R4") (pin "1") (pinfunction "1_1") (pintype "passive"))
    )
    (net (code "75") (name "Net-(3D1-SWC)") (class "Default")
      (node (ref "3D1") (pin "1") (pinfunction "SWC_1") (pintype "passive"))
      (node (ref "3L1") (pin "2") (pinfunction "2_2") (pintype "passive"))
      (node (ref "3VD1") (pin "A") (pinfunction "A_A") (pintype "passive"))
    )
    (net (code "76") (name "Net-(3D1-TC)") (class "Default")
      (node (ref "3C4") (pin "1") (pinfunction "1_1") (pintype "passive"))
      (node (ref "3D1") (pin "3") (pinfunction "TC_3") (pintype "passive"))
    )
    (net (code "77") (name "Net-(4C1-Pad2)") (class "Default")
      (node (ref "4C1") (pin "2") (pinfunction "2_2") (pintype "passive"))
      (node (ref "4R1") (pin "2") (pinfunction "2_2") (pintype "passive"))
      (node (ref "4R2") (pin "1") (pinfunction "1_1") (pintype "passive"))
    )
    (net (code "78") (name "Net-(4VT1-B)") (class "Default")
      (node (ref "4R2") (pin "2") (pinfunction "2_2") (pintype "passive"))
      (node (ref "4R3") (pin "2") (pinfunction "2_2") (pintype "passive"))
      (node (ref "4VT1") (pin "1") (pinfunction "B_1") (pintype "passive"))
    )
    (net (code "79") (name "Net-(4VT1-C)") (class "Default")
      (node (ref "4R4") (pin "2") (pinfunction "2_2") (pintype "passive"))
      (node (ref "4VT1") (pin "3") (pinfunction "C_3") (pintype "passive"))
      (node (ref "4VT2") (pin "1") (pinfunction "G_1") (pintype "passive"))
    )
    (net (code "80") (name "Net-(4VT3-G)") (class "Default")
      (node (ref "4R5") (pin "2") (pinfunction "2_2") (pintype "passive"))
      (node (ref "4VT3") (pin "1") (pinfunction "G_1") (pintype "passive"))
    )
    (net (code "81") (name "Net-(JP23-Pad1)") (class "Default")
      (node (ref "JP23") (pin "1") (pinfunction "1_1") (pintype "passive"))
      (node (ref "RJ7") (pin "2") (pinfunction "2_2") (pintype "passive"))
    )
    (net (code "82") (name "Net-(RJ3-Pad2)") (class "Default")
      (node (ref "RJ3") (pin "2") (pinfunction "2_2") (pintype "passive"))
      (node (ref "RJ4") (pin "1") (pinfunction "1_1") (pintype "passive"))
    )
    (net (code "83") (name "Net-(RJ8-Pad1)") (class "Default")
      (node (ref "RJ8") (pin "1") (pinfunction "1_1") (pintype "passive"))
      (node (ref "USB") (pin "1") (pinfunction "1_1") (pintype "passive"))
    )
    (net (code "84") (name "Net-(S1-P)") (class "Default")
      (node (ref "1C2") (pin "1") (pinfunction "1_1") (pintype "passive"))
      (node (ref "1C8") (pin "1") (pinfunction "1_1") (pintype "passive"))
      (node (ref "RJ9") (pin "2") (pinfunction "2_2") (pintype "passive"))
      (node (ref "S1") (pin "3") (pinfunction "P_3") (pintype "passive"))
      (node (ref "S1") (pin "4") (pinfunction "P1_4") (pintype "passive"))
      (node (ref "U$1") (pin "P$1") (pinfunction "P$1_P$1") (pintype "bidirectional"))
    )
    (net (code "85") (name "unconnected-(1D1-(ADC0)PA0-Pad37)") (class "Default")
      (node (ref "1D1") (pin "37") (pinfunction "(ADC0)PA0_37") (pintype "bidirectional"))
    )
    (net (code "86") (name "unconnected-(1D1-(ADC1)PA1-Pad36)") (class "Default")
      (node (ref "1D1") (pin "36") (pinfunction "(ADC1)PA1_36") (pintype "bidirectional"))
    )
    (net (code "87") (name "unconnected-(1D1-(ADC2)PA2-Pad35)") (class "Default")
      (node (ref "1D1") (pin "35") (pinfunction "(ADC2)PA2_35") (pintype "bidirectional"))
    )
    (net (code "88") (name "unconnected-(1D1-(ADC3)PA3-Pad34)") (class "Default")
      (node (ref "1D1") (pin "34") (pinfunction "(ADC3)PA3_34") (pintype "bidirectional"))
    )
    (net (code "89") (name "unconnected-(1D1-(OC1B)PD4-Pad13)") (class "Default")
      (node (ref "1D1") (pin "13") (pinfunction "(OC1B)PD4_13") (pintype "bidirectional"))
    )
    (net (code "90") (name "unconnected-(1D2A-~{QH}-Pad7)") (class "Default")
      (node (ref "1D2") (pin "7") (pinfunction "~{QH}_7") (pintype "output"))
    )
    (net (code "91") (name "unconnected-(1HL1-C-PadK)") (class "Default")
      (node (ref "1HL1") (pin "K") (pinfunction "C_K") (pintype "passive"))
    )
    (net (code "92") (name "unconnected-(1HL2-C-PadK)") (class "Default")
      (node (ref "1HL2") (pin "K") (pinfunction "C_K") (pintype "passive"))
    )
    (net (code "93") (name "unconnected-(1HL3-PadA)") (class "Default")
      (node (ref "1HL3") (pin "A") (pinfunction "A_A") (pintype "passive"))
    )
    (net (code "94") (name "unconnected-(1R2-Pad2)") (class "Default")
      (node (ref "1R2") (pin "2") (pinfunction "2_2") (pintype "passive"))
    )
    (net (code "95") (name "unconnected-(1R3-Pad2)") (class "Default")
      (node (ref "1R3") (pin "2") (pinfunction "2_2") (pintype "passive"))
    )
    (net (code "96") (name "unconnected-(1R21-Pad2)") (class "Default")
      (node (ref "1R21") (pin "2") (pinfunction "2_2") (pintype "passive"))
    )
    (net (code "97") (name "unconnected-(1VD1-PadC)") (class "Default")
      (node (ref "1VD1") (pin "C") (pinfunction "C_C") (pintype "passive"))
    )
    (net (code "98") (name "unconnected-(2D1-SHTD_N-Pad12)") (class "Default")
      (node (ref "2D1") (pin "12") (pinfunction "SHTD_N_12") (pintype "bidirectional"))
    )
    (net (code "99") (name "unconnected-(IC1-Pad1)") (class "Default")
      (node (ref "IC1") (pin "1") (pinfunction "1_1") (pintype "passive"))
    )
    (net (code "100") (name "unconnected-(IC1-Pad2)") (class "Default")
      (node (ref "IC1") (pin "2") (pinfunction "2_2") (pintype "passive"))
    )
    (net (code "101") (name "unconnected-(IC1-Pad3)") (class "Default")
      (node (ref "IC1") (pin "3") (pinfunction "3_3") (pintype "passive"))
    )
    (net (code "102") (name "unconnected-(IC1-Pad4)") (class "Default")
      (node (ref "IC1") (pin "4") (pinfunction "4_4") (pintype "passive"))
    )
    (net (code "103") (name "unconnected-(IC1-Pad5)") (class "Default")
      (node (ref "IC1") (pin "5") (pinfunction "5_5") (pintype "passive"))
    )
    (net (code "104") (name "unconnected-(IC1-Pad6)") (class "Default")
      (node (ref "IC1") (pin "6") (pinfunction "6_6") (pintype "passive"))
    )
    (net (code "105") (name "unconnected-(IC1-Pad7)") (class "Default")
      (node (ref "IC1") (pin "7") (pinfunction "7_7") (pintype "passive"))
    )
    (net (code "106") (name "unconnected-(IC1-Pad8)") (class "Default")
      (node (ref "IC1") (pin "8") (pinfunction "8_8") (pintype "passive"))
    )
    (net (code "107") (name "unconnected-(IC1-Pad9)") (class "Default")
      (node (ref "IC1") (pin "9") (pinfunction "9_9") (pintype "passive"))
    )
    (net (code "108") (name "unconnected-(IC1-Pad10)") (class "Default")
      (node (ref "IC1") (pin "10") (pinfunction "10_10") (pintype "passive"))
    )
    (net (code "109") (name "unconnected-(IC1-Pad11)") (class "Default")
      (node (ref "IC1") (pin "11") (pinfunction "11_11") (pintype "passive"))
    )
    (net (code "110") (name "unconnected-(IC1-Pad12)") (class "Default")
      (node (ref "IC1") (pin "12") (pinfunction "12_12") (pintype "passive"))
    )
    (net (code "111") (name "unconnected-(IC1-Pad13)") (class "Default")
      (node (ref "IC1") (pin "13") (pinfunction "13_13") (pintype "passive"))
    )
    (net (code "112") (name "unconnected-(IC1-Pad14)") (class "Default")
      (node (ref "IC1") (pin "14") (pinfunction "14_14") (pintype "passive"))
    )
    (net (code "113") (name "unconnected-(IC1-Pad15)") (class "Default")
      (node (ref "IC1") (pin "15") (pinfunction "15_15") (pintype "passive"))
    )
    (net (code "114") (name "unconnected-(IC1-Pad16)") (class "Default")
      (node (ref "IC1") (pin "16") (pinfunction "16_16") (pintype "passive"))
    )
    (net (code "115") (name "unconnected-(IC1-Pad17)") (class "Default")
      (node (ref "IC1") (pin "17") (pinfunction "17_17") (pintype "passive"))
    )
    (net (code "116") (name "unconnected-(IC1-Pad18)") (class "Default")
      (node (ref "IC1") (pin "18") (pinfunction "18_18") (pintype "passive"))
    )
    (net (code "117") (name "unconnected-(IC1-Pad19)") (class "Default")
      (node (ref "IC1") (pin "19") (pinfunction "19_19") (pintype "passive"))
    )
    (net (code "118") (name "unconnected-(IC1-Pad20)") (class "Default")
      (node (ref "IC1") (pin "20") (pinfunction "20_20") (pintype "passive"))
    )
    (net (code "119") (name "unconnected-(IC1-Pad21)") (class "Default")
      (node (ref "IC1") (pin "21") (pinfunction "21_21") (pintype "passive"))
    )
    (net (code "120") (name "unconnected-(IC1-Pad22)") (class "Default")
      (node (ref "IC1") (pin "22") (pinfunction "22_22") (pintype "passive"))
    )
    (net (code "121") (name "unconnected-(IC1-Pad23)") (class "Default")
      (node (ref "IC1") (pin "23") (pinfunction "23_23") (pintype "passive"))
    )
    (net (code "122") (name "unconnected-(IC1-Pad24)") (class "Default")
      (node (ref "IC1") (pin "24") (pinfunction "24_24") (pintype "passive"))
    )
    (net (code "123") (name "unconnected-(ISP6-Pad1)") (class "Default")
      (node (ref "ISP6") (pin "1") (pinfunction "1_1") (pintype "passive"))
    )
    (net (code "124") (name "unconnected-(ISP6-Pad2)") (class "Default")
      (node (ref "ISP6") (pin "2") (pinfunction "2_2") (pintype "passive"))
    )
    (net (code "125") (name "unconnected-(ISP6-Pad3)") (class "Default")
      (node (ref "ISP6") (pin "3") (pinfunction "3_3") (pintype "passive"))
    )
    (net (code "126") (name "unconnected-(ISP6-Pad4)") (class "Default")
      (node (ref "ISP6") (pin "4") (pinfunction "4_4") (pintype "passive"))
    )
    (net (code "127") (name "unconnected-(ISP6-Pad5)") (class "Default")
      (node (ref "ISP6") (pin "5") (pinfunction "5_5") (pintype "passive"))
    )
    (net (code "128") (name "unconnected-(ISP6-Pad6)") (class "Default")
      (node (ref "ISP6") (pin "6") (pinfunction "6_6") (pintype "passive"))
    )
    (net (code "129") (name "unconnected-(J1-Pad2)") (class "Default")
      (node (ref "J1") (pin "2") (pinfunction "2_2") (pintype "passive"))
    )
    (net (code "130") (name "unconnected-(J2-Pad2)") (class "Default")
      (node (ref "J2") (pin "2") (pinfunction "2_2") (pintype "passive"))
    )
    (net (code "131") (name "unconnected-(JI-Pad2)") (class "Default")
      (node (ref "JI") (pin "2") (pinfunction "2_2") (pintype "passive"))
    )
    (net (code "132") (name "unconnected-(JO-Pad2)") (class "Default")
      (node (ref "JO") (pin "2") (pinfunction "2_2") (pintype "passive"))
    )
    (net (code "133") (name "unconnected-(JR-Pad2)") (class "Default")
      (node (ref "JR") (pin "2") (pinfunction "2_2") (pintype "passive"))
    )
    (net (code "134") (name "unconnected-(JS-Pad2)") (class "Default")
      (node (ref "JS") (pin "2") (pinfunction "2_2") (pintype "passive"))
    )
    (net (code "135") (name "unconnected-(RJ1-Pad1)") (class "Default")
      (node (ref "RJ1") (pin "1") (pinfunction "1_1") (pintype "passive"))
    )
    (net (code "136") (name "unconnected-(RJ1-Pad2)") (class "Default")
      (node (ref "RJ1") (pin "2") (pinfunction "2_2") (pintype "passive"))
    )
    (net (code "137") (name "unconnected-(RJ2-Pad1)") (class "Default")
      (node (ref "RJ2") (pin "1") (pinfunction "1_1") (pintype "passive"))
    )
    (net (code "138") (name "unconnected-(S2-P-Pad3)") (class "Default")
      (node (ref "S2") (pin "3") (pinfunction "P_3") (pintype "passive"))
    )
    (net (code "139") (name "unconnected-(S2-P1-Pad4)") (class "Default")
      (node (ref "S2") (pin "4") (pinfunction "P1_4") (pintype "passive"))
    )
  )
)
